# FMC_PINBREAKOUT.net
KiCad netlist of a schematic drawn in Altium Designer
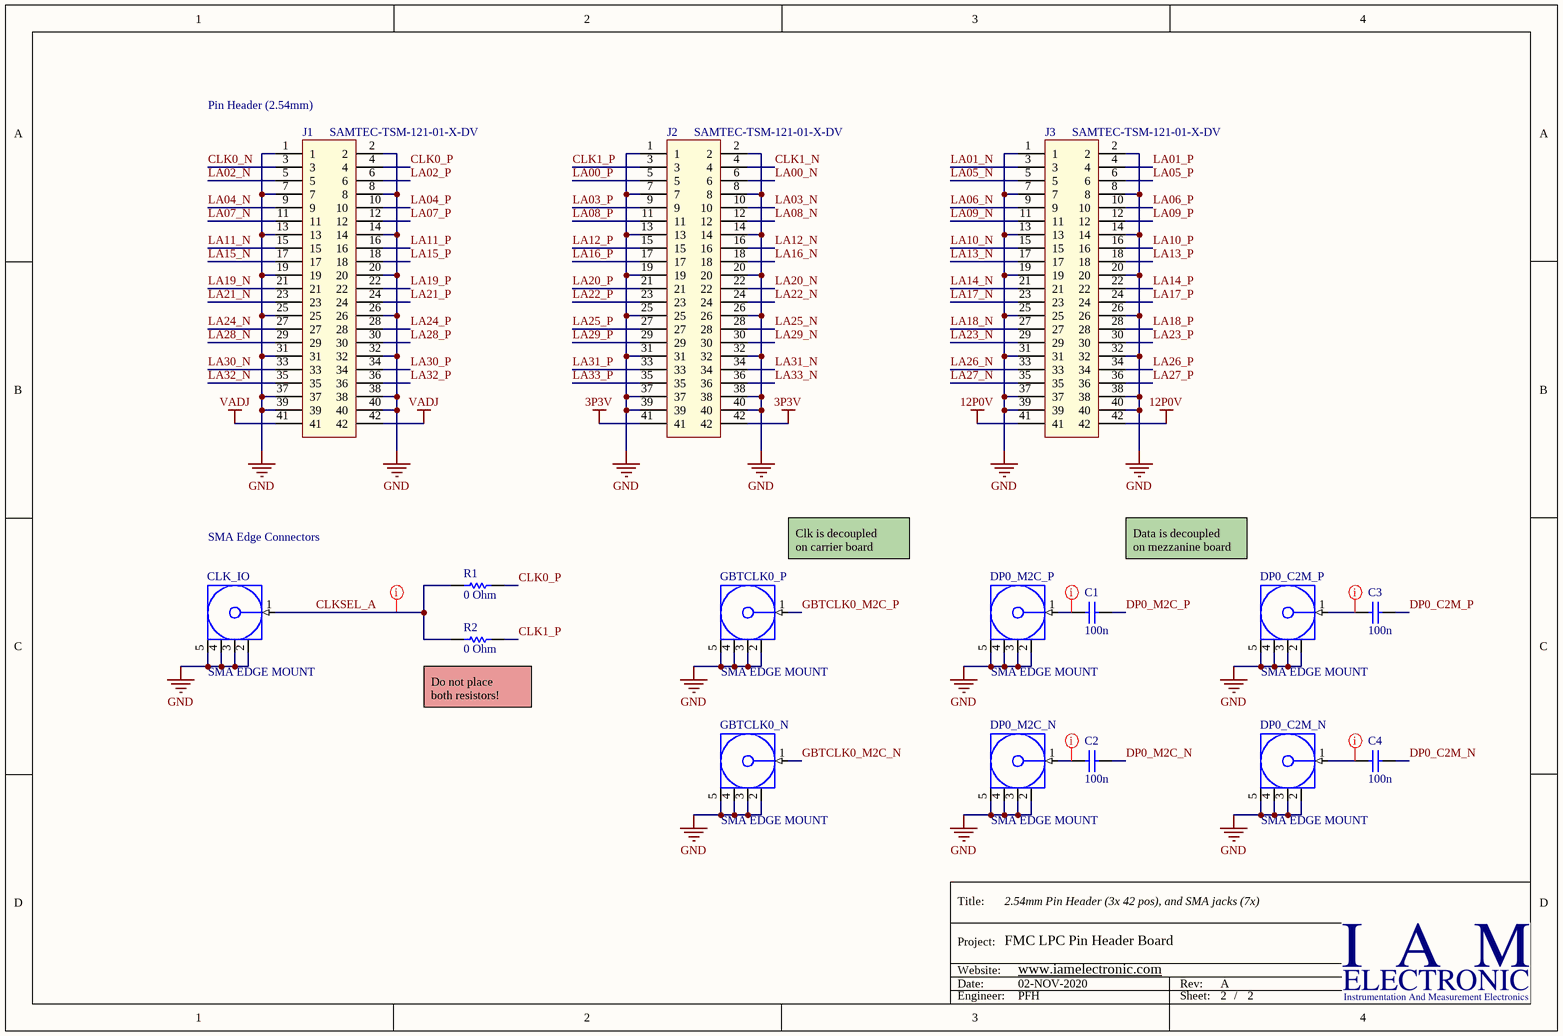
[diagram p0: FMC_PINBREAKOUT.SchDoc]

(export (version "E")
  (design (tool "Eeschema 10.0.6"))
  (components
    (comp (ref "C1")
      (value "100n")
      (footprint "CAPC1005X55X25ML05T10")
      (description "Chip Capacitor, 0.1 uF, +/- 10%, 16 V, -55 to 125 degC, 0402 (1005 Metric), RoHS, Tape and Reel")
      (fields (field (name "VOLTAGE") "16V") (field (name "TOLERANCE") "10%"))
      (libsource (lib "Altium Content Vault") (part "CAP-NP-2"))
    )
    (comp (ref "C2")
      (value "100n")
      (footprint "CAPC1005X55X25ML05T10")
      (description "Chip Capacitor, 0.1 uF, +/- 10%, 16 V, -55 to 125 degC, 0402 (1005 Metric), RoHS, Tape and Reel")
      (fields (field (name "VOLTAGE") "16V") (field (name "TOLERANCE") "10%"))
      (libsource (lib "Altium Content Vault") (part "CAP-NP-2"))
    )
    (comp (ref "C3")
      (value "100n")
      (footprint "CAPC1005X55X25ML05T10")
      (description "Chip Capacitor, 0.1 uF, +/- 10%, 16 V, -55 to 125 degC, 0402 (1005 Metric), RoHS, Tape and Reel")
      (fields (field (name "VOLTAGE") "16V") (field (name "TOLERANCE") "10%"))
      (libsource (lib "Altium Content Vault") (part "CAP-NP-2"))
    )
    (comp (ref "C4")
      (value "100n")
      (footprint "CAPC1005X55X25ML05T10")
      (description "Chip Capacitor, 0.1 uF, +/- 10%, 16 V, -55 to 125 degC, 0402 (1005 Metric), RoHS, Tape and Reel")
      (fields (field (name "VOLTAGE") "16V") (field (name "TOLERANCE") "10%"))
      (libsource (lib "Altium Content Vault") (part "CAP-NP-2"))
    )
    (comp (ref "CLK_IO")
      (value "SMA EDGE MOUNT")
      (footprint "CON-SMA-EDGE062")
      (description "RP-SMA Female Edge Mount Connector for 0.062\" Thick Board")
      (fields (field (name "MANUFACTURER") "Samtec") (field (name "PART") "SMA-J-P-H-ST-EM1"))
      (libsource (lib "Altium Content Vault") (part "CN-1P-F-RF5"))
    )
    (comp (ref "DP0_C2M_N")
      (value "SMA EDGE MOUNT")
      (footprint "CON-SMA-EDGE062")
      (description "RP-SMA Female Edge Mount Connector for 0.062\" Thick Board")
      (fields (field (name "MANUFACTURER") "Samtec") (field (name "PART") "SMA-J-P-H-ST-EM1"))
      (libsource (lib "Altium Content Vault") (part "CN-1P-F-RF5"))
    )
    (comp (ref "DP0_C2M_P")
      (value "SMA EDGE MOUNT")
      (footprint "CON-SMA-EDGE062")
      (description "RP-SMA Female Edge Mount Connector for 0.062\" Thick Board")
      (fields (field (name "MANUFACTURER") "Samtec") (field (name "PART") "SMA-J-P-H-ST-EM1"))
      (libsource (lib "Altium Content Vault") (part "CN-1P-F-RF5"))
    )
    (comp (ref "DP0_M2C_N")
      (value "SMA EDGE MOUNT")
      (footprint "CON-SMA-EDGE062")
      (description "RP-SMA Female Edge Mount Connector for 0.062\" Thick Board")
      (fields (field (name "MANUFACTURER") "Samtec") (field (name "PART") "SMA-J-P-H-ST-EM1"))
      (libsource (lib "Altium Content Vault") (part "CN-1P-F-RF5"))
    )
    (comp (ref "DP0_M2C_P")
      (value "SMA EDGE MOUNT")
      (footprint "CON-SMA-EDGE062")
      (description "RP-SMA Female Edge Mount Connector for 0.062\" Thick Board")
      (fields (field (name "MANUFACTURER") "Samtec") (field (name "PART") "SMA-J-P-H-ST-EM1"))
      (libsource (lib "Altium Content Vault") (part "CN-1P-F-RF5"))
    )
    (comp (ref "GBTCLK0_N")
      (value "SMA EDGE MOUNT")
      (footprint "CON-SMA-EDGE062")
      (description "RP-SMA Female Edge Mount Connector for 0.062\" Thick Board")
      (fields (field (name "MANUFACTURER") "Samtec") (field (name "PART") "SMA-J-P-H-ST-EM1"))
      (libsource (lib "Altium Content Vault") (part "CN-1P-F-RF5"))
    )
    (comp (ref "GBTCLK0_P")
      (value "SMA EDGE MOUNT")
      (footprint "CON-SMA-EDGE062")
      (description "RP-SMA Female Edge Mount Connector for 0.062\" Thick Board")
      (fields (field (name "MANUFACTURER") "Samtec") (field (name "PART") "SMA-J-P-H-ST-EM1"))
      (libsource (lib "Altium Content Vault") (part "CN-1P-F-RF5"))
    )
    (comp (ref "J1")
      (value "SAMTEC-TSM-121-01-X-DV")
      (footprint "SAMTEC-TSM-121-01-X-DV")
      (description "SMT 2.54mm SQ POST HEADER")
      (fields (field (name "MANUFACTURER") "Samtec") (field (name "PART") "TSM-121-01-T-DV"))
      (libsource (lib "SAMTEC-TSM-121-01-X-DV") (part "SAMTEC-TSM-121-01-X-DV"))
    )
    (comp (ref "J2")
      (value "SAMTEC-TSM-121-01-X-DV")
      (footprint "SAMTEC-TSM-121-01-X-DV")
      (description "SMT 2.54mm SQ POST HEADER")
      (fields (field (name "MANUFACTURER") "Samtec") (field (name "PART") "TSM-121-01-T-DV"))
      (libsource (lib "SAMTEC-TSM-121-01-X-DV") (part "SAMTEC-TSM-121-01-X-DV"))
    )
    (comp (ref "J3")
      (value "SAMTEC-TSM-121-01-X-DV")
      (footprint "SAMTEC-TSM-121-01-X-DV")
      (description "SMT 2.54mm SQ POST HEADER")
      (fields (field (name "MANUFACTURER") "Samtec") (field (name "PART") "TSM-121-01-T-DV"))
      (libsource (lib "SAMTEC-TSM-121-01-X-DV") (part "SAMTEC-TSM-121-01-X-DV"))
    )
    (comp (ref "R1")
      (value "0 Ohm")
      (footprint "RESC3116X65X40LL10T20")
      (description "Chip Resistor, 0 Ohm, +/- 5%, -55 to 155 degC, 1206 (3216 Metric), RoHS, Tape and Reel")
      (fields (field (name "MANUFACTURER") "Yageo") (field (name "TOLERANCE") "5%"))
      (libsource (lib "Altium Content Vault") (part "RES-2"))
    )
    (comp (ref "R2")
      (value "0 Ohm")
      (footprint "RESC3116X65X40LL10T20")
      (description "Chip Resistor, 0 Ohm, +/- 5%, -55 to 155 degC, 1206 (3216 Metric), RoHS, Tape and Reel")
      (fields (field (name "MANUFACTURER") "Yageo") (field (name "TOLERANCE") "5%"))
      (libsource (lib "Altium Content Vault") (part "RES-2"))
    )
  )
  (nets
    (net (code "1") (name "/CLK0_N") (class "Default")
      (node (ref "J1") (pin "3") (pinfunction "3_3") (pintype "passive"))
    )
    (net (code "2") (name "/CLK0_P") (class "Default")
      (node (ref "J1") (pin "4") (pinfunction "4_4") (pintype "passive"))
      (node (ref "R1") (pin "2") (pinfunction "2_2") (pintype "passive"))
    )
    (net (code "3") (name "/CLK1_N") (class "Default")
      (node (ref "J2") (pin "4") (pinfunction "4_4") (pintype "passive"))
    )
    (net (code "4") (name "/CLK1_P") (class "Default")
      (node (ref "J2") (pin "3") (pinfunction "3_3") (pintype "passive"))
      (node (ref "R2") (pin "2") (pinfunction "2_2") (pintype "passive"))
    )
    (net (code "5") (name "/CLKSEL_A") (class "Default")
      (node (ref "CLK_IO") (pin "1") (pinfunction "Signal_1") (pintype "input"))
      (node (ref "R1") (pin "1") (pinfunction "1_1") (pintype "passive"))
      (node (ref "R2") (pin "1") (pinfunction "1_1") (pintype "passive"))
    )
    (net (code "6") (name "/DP0_C2M_N") (class "Default")
      (node (ref "C4") (pin "2") (pinfunction "2_2") (pintype "passive"))
    )
    (net (code "7") (name "/DP0_C2M_P") (class "Default")
      (node (ref "C3") (pin "2") (pinfunction "2_2") (pintype "passive"))
    )
    (net (code "8") (name "/DP0_M2C_N") (class "Default")
      (node (ref "C2") (pin "2") (pinfunction "2_2") (pintype "passive"))
    )
    (net (code "9") (name "/DP0_M2C_P") (class "Default")
      (node (ref "C1") (pin "2") (pinfunction "2_2") (pintype "passive"))
    )
    (net (code "10") (name "/GBTCLK0_M2C_N") (class "Default")
      (node (ref "GBTCLK0_N") (pin "1") (pinfunction "Signal_1") (pintype "input"))
    )
    (net (code "11") (name "/GBTCLK0_M2C_P") (class "Default")
      (node (ref "GBTCLK0_P") (pin "1") (pinfunction "Signal_1") (pintype "input"))
    )
    (net (code "12") (name "/LA00_N") (class "Default")
      (node (ref "J2") (pin "6") (pinfunction "6_6") (pintype "passive"))
    )
    (net (code "13") (name "/LA00_P") (class "Default")
      (node (ref "J2") (pin "5") (pinfunction "5_5") (pintype "passive"))
    )
    (net (code "14") (name "/LA01_N") (class "Default")
      (node (ref "J3") (pin "3") (pinfunction "3_3") (pintype "passive"))
    )
    (net (code "15") (name "/LA01_P") (class "Default")
      (node (ref "J3") (pin "4") (pinfunction "4_4") (pintype "passive"))
    )
    (net (code "16") (name "/LA02_N") (class "Default")
      (node (ref "J1") (pin "5") (pinfunction "5_5") (pintype "passive"))
    )
    (net (code "17") (name "/LA02_P") (class "Default")
      (node (ref "J1") (pin "6") (pinfunction "6_6") (pintype "passive"))
    )
    (net (code "18") (name "/LA03_N") (class "Default")
      (node (ref "J2") (pin "10") (pinfunction "10_10") (pintype "passive"))
    )
    (net (code "19") (name "/LA03_P") (class "Default")
      (node (ref "J2") (pin "9") (pinfunction "9_9") (pintype "passive"))
    )
    (net (code "20") (name "/LA04_N") (class "Default")
      (node (ref "J1") (pin "9") (pinfunction "9_9") (pintype "passive"))
    )
    (net (code "21") (name "/LA04_P") (class "Default")
      (node (ref "J1") (pin "10") (pinfunction "10_10") (pintype "passive"))
    )
    (net (code "22") (name "/LA05_N") (class "Default")
      (node (ref "J3") (pin "5") (pinfunction "5_5") (pintype "passive"))
    )
    (net (code "23") (name "/LA05_P") (class "Default")
      (node (ref "J3") (pin "6") (pinfunction "6_6") (pintype "passive"))
    )
    (net (code "24") (name "/LA06_N") (class "Default")
      (node (ref "J3") (pin "9") (pinfunction "9_9") (pintype "passive"))
    )
    (net (code "25") (name "/LA06_P") (class "Default")
      (node (ref "J3") (pin "10") (pinfunction "10_10") (pintype "passive"))
    )
    (net (code "26") (name "/LA07_N") (class "Default")
      (node (ref "J1") (pin "11") (pinfunction "11_11") (pintype "passive"))
    )
    (net (code "27") (name "/LA07_P") (class "Default")
      (node (ref "J1") (pin "12") (pinfunction "12_12") (pintype "passive"))
    )
    (net (code "28") (name "/LA08_N") (class "Default")
      (node (ref "J2") (pin "12") (pinfunction "12_12") (pintype "passive"))
    )
    (net (code "29") (name "/LA08_P") (class "Default")
      (node (ref "J2") (pin "11") (pinfunction "11_11") (pintype "passive"))
    )
    (net (code "30") (name "/LA09_N") (class "Default")
      (node (ref "J3") (pin "11") (pinfunction "11_11") (pintype "passive"))
    )
    (net (code "31") (name "/LA09_P") (class "Default")
      (node (ref "J3") (pin "12") (pinfunction "12_12") (pintype "passive"))
    )
    (net (code "32") (name "/LA10_N") (class "Default")
      (node (ref "J3") (pin "15") (pinfunction "15_15") (pintype "passive"))
    )
    (net (code "33") (name "/LA10_P") (class "Default")
      (node (ref "J3") (pin "16") (pinfunction "16_16") (pintype "passive"))
    )
    (net (code "34") (name "/LA11_N") (class "Default")
      (node (ref "J1") (pin "15") (pinfunction "15_15") (pintype "passive"))
    )
    (net (code "35") (name "/LA11_P") (class "Default")
      (node (ref "J1") (pin "16") (pinfunction "16_16") (pintype "passive"))
    )
    (net (code "36") (name "/LA12_N") (class "Default")
      (node (ref "J2") (pin "16") (pinfunction "16_16") (pintype "passive"))
    )
    (net (code "37") (name "/LA12_P") (class "Default")
      (node (ref "J2") (pin "15") (pinfunction "15_15") (pintype "passive"))
    )
    (net (code "38") (name "/LA13_N") (class "Default")
      (node (ref "J3") (pin "17") (pinfunction "17_17") (pintype "passive"))
    )
    (net (code "39") (name "/LA13_P") (class "Default")
      (node (ref "J3") (pin "18") (pinfunction "18_18") (pintype "passive"))
    )
    (net (code "40") (name "/LA14_N") (class "Default")
      (node (ref "J3") (pin "21") (pinfunction "21_21") (pintype "passive"))
    )
    (net (code "41") (name "/LA14_P") (class "Default")
      (node (ref "J3") (pin "22") (pinfunction "22_22") (pintype "passive"))
    )
    (net (code "42") (name "/LA15_N") (class "Default")
      (node (ref "J1") (pin "17") (pinfunction "17_17") (pintype "passive"))
    )
    (net (code "43") (name "/LA15_P") (class "Default")
      (node (ref "J1") (pin "18") (pinfunction "18_18") (pintype "passive"))
    )
    (net (code "44") (name "/LA16_N") (class "Default")
      (node (ref "J2") (pin "18") (pinfunction "18_18") (pintype "passive"))
    )
    (net (code "45") (name "/LA16_P") (class "Default")
      (node (ref "J2") (pin "17") (pinfunction "17_17") (pintype "passive"))
    )
    (net (code "46") (name "/LA17_N") (class "Default")
      (node (ref "J3") (pin "23") (pinfunction "23_23") (pintype "passive"))
    )
    (net (code "47") (name "/LA17_P") (class "Default")
      (node (ref "J3") (pin "24") (pinfunction "24_24") (pintype "passive"))
    )
    (net (code "48") (name "/LA18_N") (class "Default")
      (node (ref "J3") (pin "27") (pinfunction "27_27") (pintype "passive"))
    )
    (net (code "49") (name "/LA18_P") (class "Default")
      (node (ref "J3") (pin "28") (pinfunction "28_28") (pintype "passive"))
    )
    (net (code "50") (name "/LA19_N") (class "Default")
      (node (ref "J1") (pin "21") (pinfunction "21_21") (pintype "passive"))
    )
    (net (code "51") (name "/LA19_P") (class "Default")
      (node (ref "J1") (pin "22") (pinfunction "22_22") (pintype "passive"))
    )
    (net (code "52") (name "/LA20_N") (class "Default")
      (node (ref "J2") (pin "22") (pinfunction "22_22") (pintype "passive"))
    )
    (net (code "53") (name "/LA20_P") (class "Default")
      (node (ref "J2") (pin "21") (pinfunction "21_21") (pintype "passive"))
    )
    (net (code "54") (name "/LA21_N") (class "Default")
      (node (ref "J1") (pin "23") (pinfunction "23_23") (pintype "passive"))
    )
    (net (code "55") (name "/LA21_P") (class "Default")
      (node (ref "J1") (pin "24") (pinfunction "24_24") (pintype "passive"))
    )
    (net (code "56") (name "/LA22_N") (class "Default")
      (node (ref "J2") (pin "24") (pinfunction "24_24") (pintype "passive"))
    )
    (net (code "57") (name "/LA22_P") (class "Default")
      (node (ref "J2") (pin "23") (pinfunction "23_23") (pintype "passive"))
    )
    (net (code "58") (name "/LA23_N") (class "Default")
      (node (ref "J3") (pin "29") (pinfunction "29_29") (pintype "passive"))
    )
    (net (code "59") (name "/LA23_P") (class "Default")
      (node (ref "J3") (pin "30") (pinfunction "30_30") (pintype "passive"))
    )
    (net (code "60") (name "/LA24_N") (class "Default")
      (node (ref "J1") (pin "27") (pinfunction "27_27") (pintype "passive"))
    )
    (net (code "61") (name "/LA24_P") (class "Default")
      (node (ref "J1") (pin "28") (pinfunction "28_28") (pintype "passive"))
    )
    (net (code "62") (name "/LA25_N") (class "Default")
      (node (ref "J2") (pin "28") (pinfunction "28_28") (pintype "passive"))
    )
    (net (code "63") (name "/LA25_P") (class "Default")
      (node (ref "J2") (pin "27") (pinfunction "27_27") (pintype "passive"))
    )
    (net (code "64") (name "/LA26_N") (class "Default")
      (node (ref "J3") (pin "33") (pinfunction "33_33") (pintype "passive"))
    )
    (net (code "65") (name "/LA26_P") (class "Default")
      (node (ref "J3") (pin "34") (pinfunction "34_34") (pintype "passive"))
    )
    (net (code "66") (name "/LA27_N") (class "Default")
      (node (ref "J3") (pin "35") (pinfunction "35_35") (pintype "passive"))
    )
    (net (code "67") (name "/LA27_P") (class "Default")
      (node (ref "J3") (pin "36") (pinfunction "36_36") (pintype "passive"))
    )
    (net (code "68") (name "/LA28_N") (class "Default")
      (node (ref "J1") (pin "29") (pinfunction "29_29") (pintype "passive"))
    )
    (net (code "69") (name "/LA28_P") (class "Default")
      (node (ref "J1") (pin "30") (pinfunction "30_30") (pintype "passive"))
    )
    (net (code "70") (name "/LA29_N") (class "Default")
      (node (ref "J2") (pin "30") (pinfunction "30_30") (pintype "passive"))
    )
    (net (code "71") (name "/LA29_P") (class "Default")
      (node (ref "J2") (pin "29") (pinfunction "29_29") (pintype "passive"))
    )
    (net (code "72") (name "/LA30_N") (class "Default")
      (node (ref "J1") (pin "33") (pinfunction "33_33") (pintype "passive"))
    )
    (net (code "73") (name "/LA30_P") (class "Default")
      (node (ref "J1") (pin "34") (pinfunction "34_34") (pintype "passive"))
    )
    (net (code "74") (name "/LA31_N") (class "Default")
      (node (ref "J2") (pin "34") (pinfunction "34_34") (pintype "passive"))
    )
    (net (code "75") (name "/LA31_P") (class "Default")
      (node (ref "J2") (pin "33") (pinfunction "33_33") (pintype "passive"))
    )
    (net (code "76") (name "/LA32_N") (class "Default")
      (node (ref "J1") (pin "35") (pinfunction "35_35") (pintype "passive"))
    )
    (net (code "77") (name "/LA32_P") (class "Default")
      (node (ref "J1") (pin "36") (pinfunction "36_36") (pintype "passive"))
    )
    (net (code "78") (name "/LA33_N") (class "Default")
      (node (ref "J2") (pin "36") (pinfunction "36_36") (pintype "passive"))
    )
    (net (code "79") (name "/LA33_P") (class "Default")
      (node (ref "J2") (pin "35") (pinfunction "35_35") (pintype "passive"))
    )
    (net (code "80") (name "3P3V") (class "Default")
      (node (ref "J2") (pin "41") (pinfunction "41_41") (pintype "passive"))
      (node (ref "J2") (pin "42") (pinfunction "42_42") (pintype "passive"))
    )
    (net (code "81") (name "12P0V") (class "Default")
      (node (ref "J3") (pin "41") (pinfunction "41_41") (pintype "passive"))
      (node (ref "J3") (pin "42") (pinfunction "42_42") (pintype "passive"))
    )
    (net (code "82") (name "GND") (class "Default")
      (node (ref "CLK_IO") (pin "2") (pinfunction "GND_2") (pintype "power_in"))
      (node (ref "CLK_IO") (pin "3") (pinfunction "GND_3") (pintype "power_in"))
      (node (ref "CLK_IO") (pin "4") (pinfunction "GND_4") (pintype "power_in"))
      (node (ref "CLK_IO") (pin "5") (pinfunction "GND_5") (pintype "power_in"))
      (node (ref "DP0_C2M_N") (pin "2") (pinfunction "GND_2") (pintype "power_in"))
      (node (ref "DP0_C2M_N") (pin "3") (pinfunction "GND_3") (pintype "power_in"))
      (node (ref "DP0_C2M_N") (pin "4") (pinfunction "GND_4") (pintype "power_in"))
      (node (ref "DP0_C2M_N") (pin "5") (pinfunction "GND_5") (pintype "power_in"))
      (node (ref "DP0_C2M_P") (pin "2") (pinfunction "GND_2") (pintype "power_in"))
      (node (ref "DP0_C2M_P") (pin "3") (pinfunction "GND_3") (pintype "power_in"))
      (node (ref "DP0_C2M_P") (pin "4") (pinfunction "GND_4") (pintype "power_in"))
      (node (ref "DP0_C2M_P") (pin "5") (pinfunction "GND_5") (pintype "power_in"))
      (node (ref "DP0_M2C_N") (pin "2") (pinfunction "GND_2") (pintype "power_in"))
      (node (ref "DP0_M2C_N") (pin "3") (pinfunction "GND_3") (pintype "power_in"))
      (node (ref "DP0_M2C_N") (pin "4") (pinfunction "GND_4") (pintype "power_in"))
      (node (ref "DP0_M2C_N") (pin "5") (pinfunction "GND_5") (pintype "power_in"))
      (node (ref "DP0_M2C_P") (pin "2") (pinfunction "GND_2") (pintype "power_in"))
      (node (ref "DP0_M2C_P") (pin "3") (pinfunction "GND_3") (pintype "power_in"))
      (node (ref "DP0_M2C_P") (pin "4") (pinfunction "GND_4") (pintype "power_in"))
      (node (ref "DP0_M2C_P") (pin "5") (pinfunction "GND_5") (pintype "power_in"))
      (node (ref "GBTCLK0_N") (pin "2") (pinfunction "GND_2") (pintype "power_in"))
      (node (ref "GBTCLK0_N") (pin "3") (pinfunction "GND_3") (pintype "power_in"))
      (node (ref "GBTCLK0_N") (pin "4") (pinfunction "GND_4") (pintype "power_in"))
      (node (ref "GBTCLK0_N") (pin "5") (pinfunction "GND_5") (pintype "power_in"))
      (node (ref "GBTCLK0_P") (pin "2") (pinfunction "GND_2") (pintype "power_in"))
      (node (ref "GBTCLK0_P") (pin "3") (pinfunction "GND_3") (pintype "power_in"))
      (node (ref "GBTCLK0_P") (pin "4") (pinfunction "GND_4") (pintype "power_in"))
      (node (ref "GBTCLK0_P") (pin "5") (pinfunction "GND_5") (pintype "power_in"))
      (node (ref "J1") (pin "1") (pinfunction "1_1") (pintype "passive"))
      (node (ref "J1") (pin "13") (pinfunction "13_13") (pintype "passive"))
      (node (ref "J1") (pin "14") (pinfunction "14_14") (pintype "passive"))
      (node (ref "J1") (pin "19") (pinfunction "19_19") (pintype "passive"))
      (node (ref "J1") (pin "2") (pinfunction "2_2") (pintype "passive"))
      (node (ref "J1") (pin "20") (pinfunction "20_20") (pintype "passive"))
      (node (ref "J1") (pin "25") (pinfunction "25_25") (pintype "passive"))
      (node (ref "J1") (pin "26") (pinfunction "26_26") (pintype "passive"))
      (node (ref "J1") (pin "31") (pinfunction "31_31") (pintype "passive"))
      (node (ref "J1") (pin "32") (pinfunction "32_32") (pintype "passive"))
      (node (ref "J1") (pin "37") (pinfunction "37_37") (pintype "passive"))
      (node (ref "J1") (pin "38") (pinfunction "38_38") (pintype "passive"))
      (node (ref "J1") (pin "39") (pinfunction "39_39") (pintype "passive"))
      (node (ref "J1") (pin "40") (pinfunction "40_40") (pintype "passive"))
      (node (ref "J1") (pin "7") (pinfunction "7_7") (pintype "passive"))
      (node (ref "J1") (pin "8") (pinfunction "8_8") (pintype "passive"))
      (node (ref "J2") (pin "1") (pinfunction "1_1") (pintype "passive"))
      (node (ref "J2") (pin "13") (pinfunction "13_13") (pintype "passive"))
      (node (ref "J2") (pin "14") (pinfunction "14_14") (pintype "passive"))
      (node (ref "J2") (pin "19") (pinfunction "19_19") (pintype "passive"))
      (node (ref "J2") (pin "2") (pinfunction "2_2") (pintype "passive"))
      (node (ref "J2") (pin "20") (pinfunction "20_20") (pintype "passive"))
      (node (ref "J2") (pin "25") (pinfunction "25_25") (pintype "passive"))
      (node (ref "J2") (pin "26") (pinfunction "26_26") (pintype "passive"))
      (node (ref "J2") (pin "31") (pinfunction "31_31") (pintype "passive"))
      (node (ref "J2") (pin "32") (pinfunction "32_32") (pintype "passive"))
      (node (ref "J2") (pin "37") (pinfunction "37_37") (pintype "passive"))
      (node (ref "J2") (pin "38") (pinfunction "38_38") (pintype "passive"))
      (node (ref "J2") (pin "39") (pinfunction "39_39") (pintype "passive"))
      (node (ref "J2") (pin "40") (pinfunction "40_40") (pintype "passive"))
      (node (ref "J2") (pin "7") (pinfunction "7_7") (pintype "passive"))
      (node (ref "J2") (pin "8") (pinfunction "8_8") (pintype "passive"))
      (node (ref "J3") (pin "1") (pinfunction "1_1") (pintype "passive"))
      (node (ref "J3") (pin "13") (pinfunction "13_13") (pintype "passive"))
      (node (ref "J3") (pin "14") (pinfunction "14_14") (pintype "passive"))
      (node (ref "J3") (pin "19") (pinfunction "19_19") (pintype "passive"))
      (node (ref "J3") (pin "2") (pinfunction "2_2") (pintype "passive"))
      (node (ref "J3") (pin "20") (pinfunction "20_20") (pintype "passive"))
      (node (ref "J3") (pin "25") (pinfunction "25_25") (pintype "passive"))
      (node (ref "J3") (pin "26") (pinfunction "26_26") (pintype "passive"))
      (node (ref "J3") (pin "31") (pinfunction "31_31") (pintype "passive"))
      (node (ref "J3") (pin "32") (pinfunction "32_32") (pintype "passive"))
      (node (ref "J3") (pin "37") (pinfunction "37_37") (pintype "passive"))
      (node (ref "J3") (pin "38") (pinfunction "38_38") (pintype "passive"))
      (node (ref "J3") (pin "39") (pinfunction "39_39") (pintype "passive"))
      (node (ref "J3") (pin "40") (pinfunction "40_40") (pintype "passive"))
      (node (ref "J3") (pin "7") (pinfunction "7_7") (pintype "passive"))
      (node (ref "J3") (pin "8") (pinfunction "8_8") (pintype "passive"))
    )
    (net (code "83") (name "Net-(DP0_C2M_N-Signal)") (class "Default")
      (node (ref "C4") (pin "1") (pinfunction "1_1") (pintype "passive"))
      (node (ref "DP0_C2M_N") (pin "1") (pinfunction "Signal_1") (pintype "input"))
    )
    (net (code "84") (name "Net-(DP0_C2M_P-Signal)") (class "Default")
      (node (ref "C3") (pin "1") (pinfunction "1_1") (pintype "passive"))
      (node (ref "DP0_C2M_P") (pin "1") (pinfunction "Signal_1") (pintype "input"))
    )
    (net (code "85") (name "Net-(DP0_M2C_N-Signal)") (class "Default")
      (node (ref "C2") (pin "1") (pinfunction "1_1") (pintype "passive"))
      (node (ref "DP0_M2C_N") (pin "1") (pinfunction "Signal_1") (pintype "input"))
    )
    (net (code "86") (name "Net-(DP0_M2C_P-Signal)") (class "Default")
      (node (ref "C1") (pin "1") (pinfunction "1_1") (pintype "passive"))
      (node (ref "DP0_M2C_P") (pin "1") (pinfunction "Signal_1") (pintype "input"))
    )
    (net (code "87") (name "VADJ") (class "Default")
      (node (ref "J1") (pin "41") (pinfunction "41_41") (pintype "passive"))
      (node (ref "J1") (pin "42") (pinfunction "42_42") (pintype "passive"))
    )
  )
)
